# Sensor.net
KiCad netlist of a schematic drawn in Altium Designer
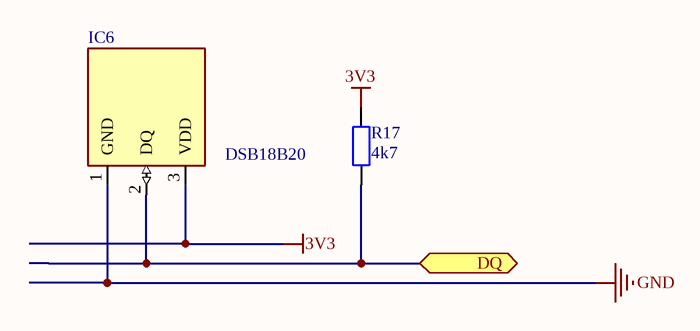
[diagram p0: Sensor.SchDoc]

(export (version "E")
  (design (tool "Eeschema 10.0.6"))
  (components
    (comp (ref "IC6")
      (value "DSB18B20")
      (footprint "TO-92")
      (description "https://linhkien.cxt.vn/3083-ds18b20-temperature-sensors-55-to-125-c-to-92-3.html")
      (libsource (lib "Main") (part "DSB18B20"))
    )
    (comp (ref "R17")
      (value "4k7")
      (footprint "RES-SMD-0805")
      (description "Resistor SMD")
      (fields
        (field (name "MANUFACTURER") "Generic Components")
        (field (name "PUBLISHER") "Altium Hobart Technology Centre")
      )
      (libsource (lib "Main") (part "Resistor - SMD"))
    )
  )
  (nets
    (net (code "1") (name "/DQ") (class "Default")
      (node (ref "IC6") (pin "2") (pinfunction "DQ_2") (pintype "bidirectional"))
      (node (ref "R17") (pin "1") (pinfunction "1_1") (pintype "passive"))
    )
    (net (code "2") (name "3V3") (class "Default")
      (node (ref "IC6") (pin "3") (pinfunction "VDD_3") (pintype "power_in"))
      (node (ref "R17") (pin "2") (pinfunction "2_2") (pintype "passive"))
    )
    (net (code "3") (name "GND") (class "Default")
      (node (ref "IC6") (pin "1") (pinfunction "GND_1") (pintype "power_in"))
    )
  )
)
